# 03_GYROSCOPE.net
KiCad netlist of a schematic drawn in Altium Designer
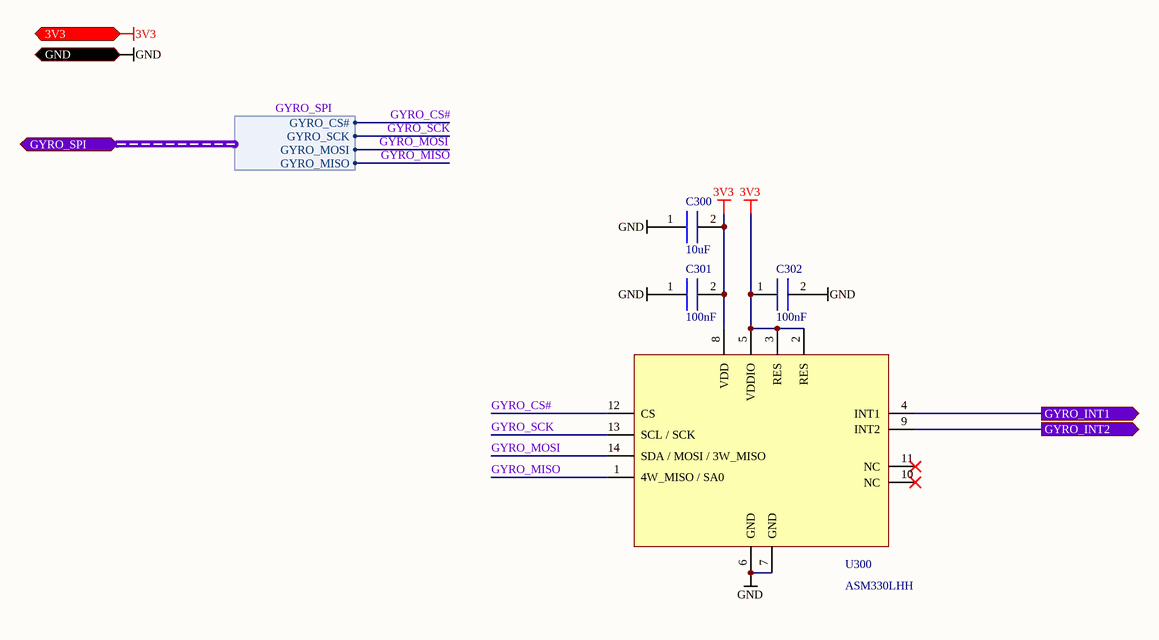
[diagram p0: 03_GYROSCOPE.SchDoc]

(export (version "E")
  (design (tool "Eeschema 10.0.6"))
  (components
    (comp (ref "C300")
      (value "10uF")
      (footprint "CAP_0402")
      (description "CAPACITOR 10uF 20% 6.3V 0402 GRM155R60J106ME05D")
      (fields (field (name "TOLERANCE") "20%") (field (name "MANUFACTURER") "MURATA"))
      (libsource (lib "Capacitors") (part "10uF 20% 6.3V 0402 GRM155R60J106ME05D"))
    )
    (comp (ref "C301")
      (value "100nF")
      (footprint "CAP_0402")
      (description "CAPACITOR 100nF 10% X7R 0402")
      (fields (field (name "TOLERANCE") "10%") (field (name "MANUFACTURER") "MURATA"))
      (libsource (lib "Capacitors") (part "100nF_10%_16V_0402_GRM155R71C104KA88J"))
    )
    (comp (ref "C302")
      (value "100nF")
      (footprint "CAP_0402")
      (description "CAPACITOR 100nF 10% X7R 0402")
      (fields (field (name "TOLERANCE") "10%") (field (name "MANUFACTURER") "MURATA"))
      (libsource (lib "Capacitors") (part "100nF_10%_16V_0402_GRM155R71C104KA88J"))
    )
    (comp (ref "U300")
      (value "GYRO_3D_3.6V_ACEL_ASM330LHH")
      (description "Gyroscope and accelerometer 3D 3.6V ASM330LHH")
      (fields (field (name "MANUFACTURER") "ST") (field (name "MANUFACTURER REFERENCE") "ASM330LHH"))
      (libsource (lib "Semiconductor") (part "GYRO_3D_3.6V_ACEL_ASM330LHH"))
    )
  )
  (nets
    (net (code "2") (name "/GYRO_CS#") (class "Default")
      (node (ref "U300") (pin "12") (pinfunction "CS_12") (pintype "passive"))
    )
    (net (code "3") (name "/GYRO_INT1") (class "Default")
      (node (ref "U300") (pin "4") (pinfunction "INT1_4") (pintype "passive"))
    )
    (net (code "4") (name "/GYRO_INT2") (class "Default")
      (node (ref "U300") (pin "9") (pinfunction "INT2_9") (pintype "passive"))
    )
    (net (code "5") (name "/GYRO_MISO") (class "Default")
      (node (ref "U300") (pin "1") (pinfunction "4W_MISO_/_SA0_1") (pintype "passive"))
    )
    (net (code "6") (name "/GYRO_MOSI") (class "Default")
      (node (ref "U300") (pin "14") (pinfunction "SDA_/_MOSI_/_3W_MISO_14") (pintype "passive"))
    )
    (net (code "7") (name "/GYRO_SCK") (class "Default")
      (node (ref "U300") (pin "13") (pinfunction "SCL_/_SCK_13") (pintype "passive"))
    )
    (net (code "9") (name "3V3") (class "Default")
      (node (ref "C300") (pin "2") (pinfunction "2_2") (pintype "passive"))
      (node (ref "C301") (pin "2") (pinfunction "2_2") (pintype "passive"))
      (node (ref "C302") (pin "1") (pinfunction "1_1") (pintype "passive"))
      (node (ref "U300") (pin "2") (pinfunction "RES_2") (pintype "passive"))
      (node (ref "U300") (pin "3") (pinfunction "RES_3") (pintype "passive"))
      (node (ref "U300") (pin "5") (pinfunction "VDDIO_5") (pintype "passive"))
      (node (ref "U300") (pin "8") (pinfunction "VDD_8") (pintype "passive"))
    )
    (net (code "10") (name "GND") (class "Default")
      (node (ref "C300") (pin "1") (pinfunction "1_1") (pintype "passive"))
      (node (ref "C301") (pin "1") (pinfunction "1_1") (pintype "passive"))
      (node (ref "C302") (pin "2") (pinfunction "2_2") (pintype "passive"))
      (node (ref "U300") (pin "6") (pinfunction "GND_6") (pintype "passive"))
      (node (ref "U300") (pin "7") (pinfunction "GND_7") (pintype "passive"))
    )
    (net (code "11") (name "unconnected-(U300-NC-Pad10)") (class "Default")
      (node (ref "U300") (pin "10") (pinfunction "NC_10") (pintype "passive+no_connect"))
    )
    (net (code "12") (name "unconnected-(U300-NC-Pad11)") (class "Default")
      (node (ref "U300") (pin "11") (pinfunction "NC_11") (pintype "passive+no_connect"))
    )
  )
)
